# iron.net
KiCad netlist of a schematic drawn in EAGLE
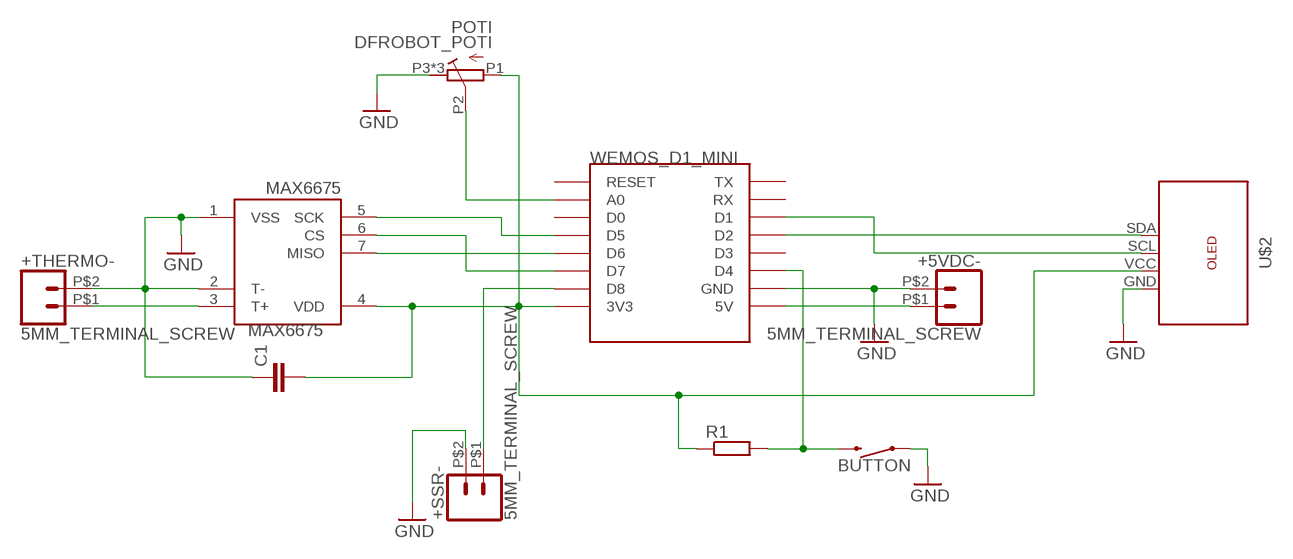
[diagram p0: schematic, sheet 1]

(export (version "E")
  (design (tool "Eeschema 10.0.6"))
  (components
    (comp (ref "+5VDC-")
      (value "5MM_TERMINAL_SCREW")
      (footprint "eagle-import:5MM_TERMINAL_SCREW")
      (libsource (lib "eagle-import") (part "5MM_TERMINAL_SCREW"))
    )
    (comp (ref "+SSR-")
      (value "5MM_TERMINAL_SCREW")
      (footprint "eagle-import:5MM_TERMINAL_SCREW")
      (libsource (lib "eagle-import") (part "5MM_TERMINAL_SCREW"))
    )
    (comp (ref "+THERMO-")
      (value "5MM_TERMINAL_SCREW")
      (footprint "eagle-import:5MM_TERMINAL_SCREW")
      (libsource (lib "eagle-import") (part "5MM_TERMINAL_SCREW"))
    )
    (comp (ref "BUTTON")
      (value "MOMENTARY-SWITCH-SPST-PTH-12MM")
      (footprint "eagle-import:TACTILE_SWITCH_PTH_12MM")
      (libsource (lib "eagle-import") (part "MOMENTARY-SWITCH-SPST-PTH-12MM"))
    )
    (comp (ref "C1")
      (value "C-EUC0603")
      (footprint "eagle-import:C0603")
      (libsource (lib "eagle-import") (part "C-EUC0603"))
    )
    (comp (ref "MAX6675")
      (value "MAX6675")
      (footprint "eagle-import:SO08")
      (libsource (lib "eagle-import") (part "MAX6675"))
    )
    (comp (ref "POTI")
      (value "DFROBOT_POTI")
      (footprint "eagle-import:DFROBOT_POTI")
      (libsource (lib "eagle-import") (part "DFROBOT_POTI"))
    )
    (comp (ref "R1")
      (value "R-EU_R0603")
      (footprint "eagle-import:R0603")
      (libsource (lib "eagle-import") (part "R-EU_R0603"))
    )
    (comp (ref "U$2")
      (value "OLED128X64")
      (footprint "eagle-import:OLED_128X64")
      (libsource (lib "eagle-import") (part "OLED128X64"))
    )
    (comp (ref "WEMOS_D1_MINI")
      (value "WEMOS-D1-MINI")
      (footprint "eagle-import:WEMOS-D1-MINI")
      (libsource (lib "eagle-import") (part "WEMOS-D1-MINI"))
    )
  )
  (nets
    (net (code "1") (name "GND") (class "Default")
      (node (ref "+5VDC-") (pin "P$2") (pinfunction "2_P$2") (pintype "passive"))
      (node (ref "+SSR-") (pin "P$2") (pinfunction "2_P$2") (pintype "passive"))
      (node (ref "+THERMO-") (pin "P$2") (pinfunction "2_P$2") (pintype "passive"))
      (node (ref "BUTTON") (pin "1") (pinfunction "1_1") (pintype "passive"))
      (node (ref "C1") (pin "1") (pinfunction "1_1") (pintype "passive"))
      (node (ref "MAX6675") (pin "1") (pinfunction "VSS_1") (pintype "bidirectional"))
      (node (ref "MAX6675") (pin "2") (pinfunction "T-_2") (pintype "bidirectional"))
      (node (ref "POTI") (pin "P3") (pinfunction "E_P3") (pintype "passive"))
      (node (ref "POTI") (pin "PG1") (pinfunction "E_PG1") (pintype "passive"))
      (node (ref "POTI") (pin "PG2") (pinfunction "E_PG2") (pintype "passive"))
      (node (ref "U$2") (pin "GND") (pinfunction "GND_GND") (pintype "bidirectional"))
      (node (ref "WEMOS_D1_MINI") (pin "GND") (pinfunction "GND_GND") (pintype "bidirectional"))
    )
    (net (code "2") (name "Net-(+5VDC--1)") (class "Default")
      (node (ref "+5VDC-") (pin "P$1") (pinfunction "1_P$1") (pintype "passive"))
      (node (ref "WEMOS_D1_MINI") (pin "5V") (pinfunction "5V_5V") (pintype "bidirectional"))
    )
    (net (code "3") (name "Net-(+SSR--1)") (class "Default")
      (node (ref "+SSR-") (pin "P$1") (pinfunction "1_P$1") (pintype "passive"))
      (node (ref "WEMOS_D1_MINI") (pin "D8") (pinfunction "D8_D8") (pintype "bidirectional"))
    )
    (net (code "4") (name "Net-(+THERMO--1)") (class "Default")
      (node (ref "+THERMO-") (pin "P$1") (pinfunction "1_P$1") (pintype "passive"))
      (node (ref "MAX6675") (pin "3") (pinfunction "T+_3") (pintype "bidirectional"))
    )
    (net (code "5") (name "Net-(BUTTON-2)") (class "Default")
      (node (ref "BUTTON") (pin "3") (pinfunction "2_3") (pintype "passive"))
      (node (ref "R1") (pin "2") (pinfunction "2_2") (pintype "passive"))
      (node (ref "WEMOS_D1_MINI") (pin "D4") (pinfunction "D4_D4") (pintype "bidirectional"))
    )
    (net (code "6") (name "Net-(MAX6675-CS)") (class "Default")
      (node (ref "MAX6675") (pin "6") (pinfunction "CS_6") (pintype "bidirectional"))
      (node (ref "WEMOS_D1_MINI") (pin "D7") (pinfunction "D7_D7") (pintype "bidirectional"))
    )
    (net (code "7") (name "Net-(MAX6675-MISO)") (class "Default")
      (node (ref "MAX6675") (pin "7") (pinfunction "MISO_7") (pintype "bidirectional"))
      (node (ref "WEMOS_D1_MINI") (pin "D6") (pinfunction "D6_D6") (pintype "bidirectional"))
    )
    (net (code "8") (name "Net-(MAX6675-SCK)") (class "Default")
      (node (ref "MAX6675") (pin "5") (pinfunction "SCK_5") (pintype "bidirectional"))
      (node (ref "WEMOS_D1_MINI") (pin "D5") (pinfunction "D5_D5") (pintype "bidirectional"))
    )
    (net (code "9") (name "Net-(MAX6675-VDD)") (class "Default")
      (node (ref "C1") (pin "2") (pinfunction "2_2") (pintype "passive"))
      (node (ref "MAX6675") (pin "4") (pinfunction "VDD_4") (pintype "bidirectional"))
      (node (ref "POTI") (pin "P1") (pinfunction "A_P1") (pintype "passive"))
      (node (ref "R1") (pin "1") (pinfunction "1_1") (pintype "passive"))
      (node (ref "U$2") (pin "VCC") (pinfunction "VCC_VCC") (pintype "bidirectional"))
      (node (ref "WEMOS_D1_MINI") (pin "3V3") (pinfunction "3V3_3V3") (pintype "bidirectional"))
    )
    (net (code "10") (name "Net-(POTI-S)") (class "Default")
      (node (ref "POTI") (pin "P2") (pinfunction "S_P2") (pintype "passive"))
      (node (ref "WEMOS_D1_MINI") (pin "A0") (pinfunction "A0_A0") (pintype "bidirectional"))
    )
    (net (code "11") (name "Net-(U$2-PadSCL)") (class "Default")
      (node (ref "U$2") (pin "SCL") (pinfunction "SCL_SCL") (pintype "bidirectional"))
      (node (ref "WEMOS_D1_MINI") (pin "D1") (pinfunction "D1_D1") (pintype "bidirectional"))
    )
    (net (code "12") (name "Net-(U$2-PadSDA)") (class "Default")
      (node (ref "U$2") (pin "SDA") (pinfunction "SDA_SDA") (pintype "bidirectional"))
      (node (ref "WEMOS_D1_MINI") (pin "D2") (pinfunction "D2_D2") (pintype "bidirectional"))
    )
    (net (code "13") (name "unconnected-(WEMOS_D1_MINI-PadD0)") (class "Default")
      (node (ref "WEMOS_D1_MINI") (pin "D0") (pinfunction "D0_D0") (pintype "bidirectional"))
    )
    (net (code "14") (name "unconnected-(WEMOS_D1_MINI-PadD3)") (class "Default")
      (node (ref "WEMOS_D1_MINI") (pin "D3") (pinfunction "D3_D3") (pintype "bidirectional"))
    )
    (net (code "15") (name "unconnected-(WEMOS_D1_MINI-PadRESET)") (class "Default")
      (node (ref "WEMOS_D1_MINI") (pin "RESET") (pinfunction "RESET_RESET") (pintype "bidirectional"))
    )
    (net (code "16") (name "unconnected-(WEMOS_D1_MINI-PadRX)") (class "Default")
      (node (ref "WEMOS_D1_MINI") (pin "RX") (pinfunction "RX_RX") (pintype "bidirectional"))
    )
    (net (code "17") (name "unconnected-(WEMOS_D1_MINI-PadTX)") (class "Default")
      (node (ref "WEMOS_D1_MINI") (pin "TX") (pinfunction "TX_TX") (pintype "bidirectional"))
    )
  )
)
